# PentaFnord_LedBoard_0_91.net
KiCad netlist of a schematic drawn in EAGLE
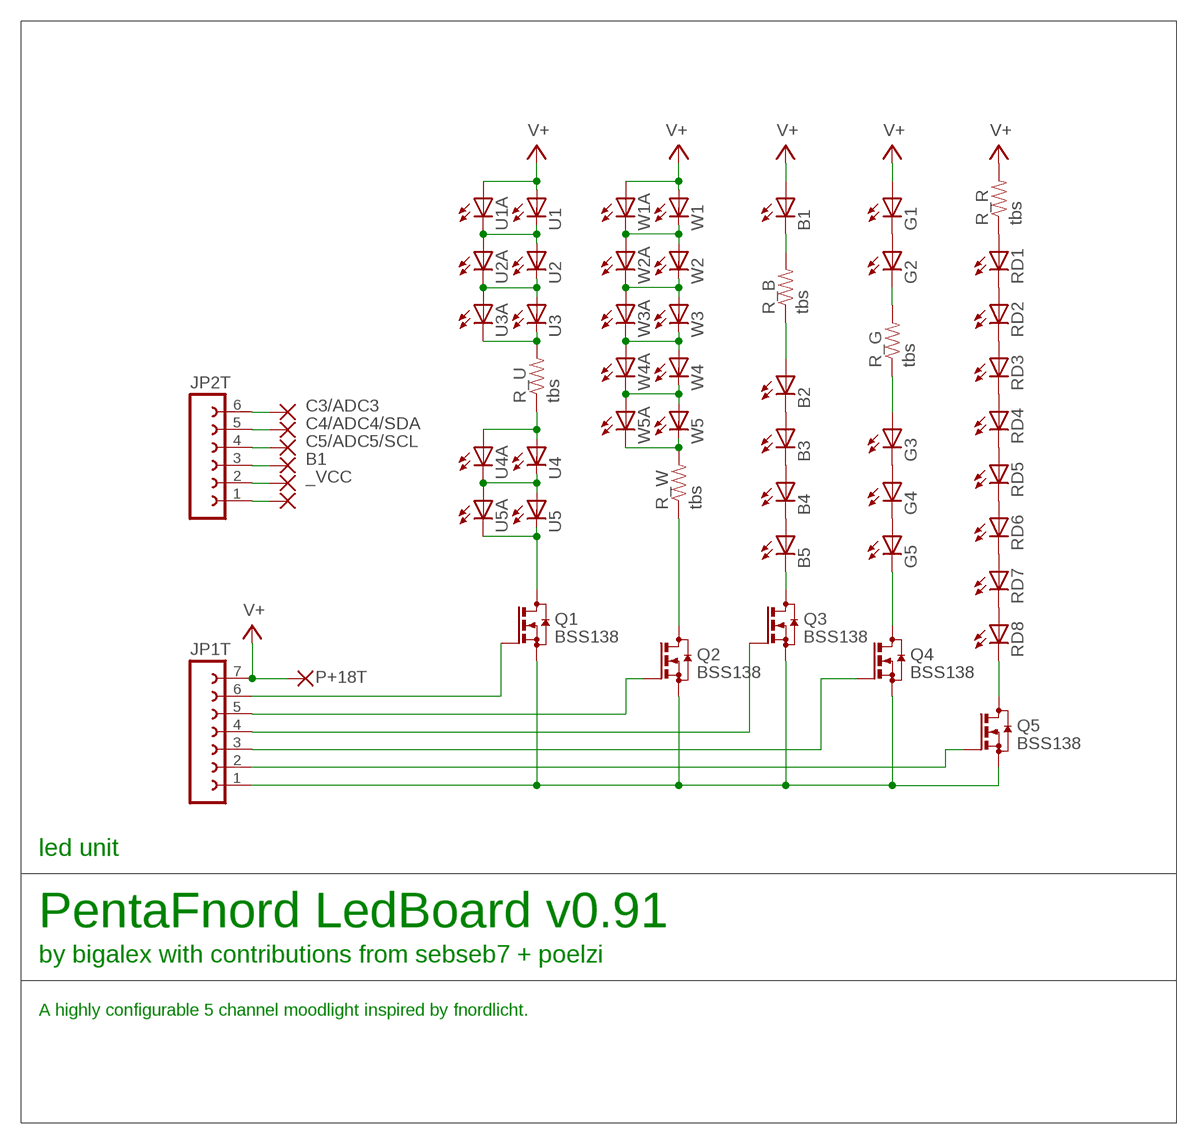
[diagram p0: schematic, sheet 1]

(export (version "E")
  (design (tool "Eeschema 10.0.6"))
  (components
    (comp (ref "B1")
      (value "LED5MM")
      (footprint "eagle-import:LED5MM")
      (libsource (lib "eagle-import") (part "LED5MM"))
    )
    (comp (ref "B2")
      (value "LED5MM")
      (footprint "eagle-import:LED5MM")
      (libsource (lib "eagle-import") (part "LED5MM"))
    )
    (comp (ref "B3")
      (value "LED5MM")
      (footprint "eagle-import:LED5MM")
      (libsource (lib "eagle-import") (part "LED5MM"))
    )
    (comp (ref "B4")
      (value "LED5MM")
      (footprint "eagle-import:LED5MM")
      (libsource (lib "eagle-import") (part "LED5MM"))
    )
    (comp (ref "B5")
      (value "LED5MM")
      (footprint "eagle-import:LED5MM")
      (libsource (lib "eagle-import") (part "LED5MM"))
    )
    (comp (ref "G1")
      (value "LED5MM")
      (footprint "eagle-import:LED5MM")
      (libsource (lib "eagle-import") (part "LED5MM"))
    )
    (comp (ref "G2")
      (value "LED5MM")
      (footprint "eagle-import:LED5MM")
      (libsource (lib "eagle-import") (part "LED5MM"))
    )
    (comp (ref "G3")
      (value "LED5MM")
      (footprint "eagle-import:LED5MM")
      (libsource (lib "eagle-import") (part "LED5MM"))
    )
    (comp (ref "G4")
      (value "LED5MM")
      (footprint "eagle-import:LED5MM")
      (libsource (lib "eagle-import") (part "LED5MM"))
    )
    (comp (ref "G5")
      (value "LED5MM")
      (footprint "eagle-import:LED5MM")
      (libsource (lib "eagle-import") (part "LED5MM"))
    )
    (comp (ref "JP1T")
      (value "FE07-1")
      (footprint "eagle-import:FE07")
      (libsource (lib "eagle-import") (part "FE07-1"))
    )
    (comp (ref "JP2T")
      (value "FE06-1")
      (footprint "eagle-import:FE06")
      (libsource (lib "eagle-import") (part "FE06-1"))
    )
    (comp (ref "P+5T")
      (value "WIREPAD2,54/0,8")
      (footprint "eagle-import:2,54_0,8")
      (libsource (lib "eagle-import") (part "WIREPAD2,54/0,8"))
    )
    (comp (ref "P+18T")
      (value "WIREPAD2,54/0,8")
      (footprint "eagle-import:2,54_0,8")
      (libsource (lib "eagle-import") (part "WIREPAD2,54/0,8"))
    )
    (comp (ref "PB1T")
      (value "WIREPAD2,54/0,8")
      (footprint "eagle-import:2,54_0,8")
      (libsource (lib "eagle-import") (part "WIREPAD2,54/0,8"))
    )
    (comp (ref "PC3T")
      (value "WIREPAD2,54/0,8")
      (footprint "eagle-import:2,54_0,8")
      (libsource (lib "eagle-import") (part "WIREPAD2,54/0,8"))
    )
    (comp (ref "PC4T")
      (value "WIREPAD2,54/0,8")
      (footprint "eagle-import:2,54_0,8")
      (libsource (lib "eagle-import") (part "WIREPAD2,54/0,8"))
    )
    (comp (ref "PC5T")
      (value "WIREPAD2,54/0,8")
      (footprint "eagle-import:2,54_0,8")
      (libsource (lib "eagle-import") (part "WIREPAD2,54/0,8"))
    )
    (comp (ref "PGNDT1")
      (value "WIREPAD2,54/0,8")
      (footprint "eagle-import:2,54_0,8")
      (libsource (lib "eagle-import") (part "WIREPAD2,54/0,8"))
    )
    (comp (ref "Q1")
      (value "BSS138")
      (footprint "eagle-import:SOT23")
      (libsource (lib "eagle-import") (part "BSS123"))
    )
    (comp (ref "Q2")
      (value "BSS138")
      (footprint "eagle-import:SOT23")
      (libsource (lib "eagle-import") (part "BSS123"))
    )
    (comp (ref "Q3")
      (value "BSS138")
      (footprint "eagle-import:SOT23")
      (libsource (lib "eagle-import") (part "BSS123"))
    )
    (comp (ref "Q4")
      (value "BSS138")
      (footprint "eagle-import:SOT23")
      (libsource (lib "eagle-import") (part "BSS123"))
    )
    (comp (ref "Q5")
      (value "BSS138")
      (footprint "eagle-import:SOT23")
      (libsource (lib "eagle-import") (part "BSS123"))
    )
    (comp (ref "RD1")
      (value "LED5MM")
      (footprint "eagle-import:LED5MM")
      (libsource (lib "eagle-import") (part "LED5MM"))
    )
    (comp (ref "RD2")
      (value "LED5MM")
      (footprint "eagle-import:LED5MM")
      (libsource (lib "eagle-import") (part "LED5MM"))
    )
    (comp (ref "RD3")
      (value "LED5MM")
      (footprint "eagle-import:LED5MM")
      (libsource (lib "eagle-import") (part "LED5MM"))
    )
    (comp (ref "RD4")
      (value "LED5MM")
      (footprint "eagle-import:LED5MM")
      (libsource (lib "eagle-import") (part "LED5MM"))
    )
    (comp (ref "RD5")
      (value "LED5MM")
      (footprint "eagle-import:LED5MM")
      (libsource (lib "eagle-import") (part "LED5MM"))
    )
    (comp (ref "RD6")
      (value "LED5MM")
      (footprint "eagle-import:LED5MM")
      (libsource (lib "eagle-import") (part "LED5MM"))
    )
    (comp (ref "RD7")
      (value "LED5MM")
      (footprint "eagle-import:LED5MM")
      (libsource (lib "eagle-import") (part "LED5MM"))
    )
    (comp (ref "RD8")
      (value "LED5MM")
      (footprint "eagle-import:LED5MM")
      (libsource (lib "eagle-import") (part "LED5MM"))
    )
    (comp (ref "R_B")
      (value "tbs")
      (footprint "eagle-import:1206")
      (libsource (lib "eagle-import") (part "RESISTOR1206"))
    )
    (comp (ref "R_G")
      (value "tbs")
      (footprint "eagle-import:1206")
      (libsource (lib "eagle-import") (part "RESISTOR1206"))
    )
    (comp (ref "R_R")
      (value "tbs")
      (footprint "eagle-import:1206")
      (libsource (lib "eagle-import") (part "RESISTOR1206"))
    )
    (comp (ref "R_U")
      (value "tbs")
      (footprint "eagle-import:1206")
      (libsource (lib "eagle-import") (part "RESISTOR1206"))
    )
    (comp (ref "R_W")
      (value "tbs")
      (footprint "eagle-import:1206")
      (libsource (lib "eagle-import") (part "RESISTOR1206"))
    )
    (comp (ref "U1")
      (value "NICHIA_NSSL157T-H3")
      (footprint "eagle-import:PLCC2")
      (libsource (lib "eagle-import") (part "LED_PLCC2"))
    )
    (comp (ref "U1A")
      (value "LED5MM")
      (footprint "eagle-import:LED5MM")
      (libsource (lib "eagle-import") (part "LED5MM"))
    )
    (comp (ref "U2")
      (value "NICHIA_NSSL157T-H3")
      (footprint "eagle-import:PLCC2")
      (libsource (lib "eagle-import") (part "LED_PLCC2"))
    )
    (comp (ref "U2A")
      (value "LED5MM")
      (footprint "eagle-import:LED5MM")
      (libsource (lib "eagle-import") (part "LED5MM"))
    )
    (comp (ref "U3")
      (value "NICHIA_NSSL157T-H3")
      (footprint "eagle-import:PLCC2")
      (libsource (lib "eagle-import") (part "LED_PLCC2"))
    )
    (comp (ref "U3A")
      (value "LED5MM")
      (footprint "eagle-import:LED5MM")
      (libsource (lib "eagle-import") (part "LED5MM"))
    )
    (comp (ref "U4")
      (value "NICHIA_NSSL157T-H3")
      (footprint "eagle-import:PLCC2")
      (libsource (lib "eagle-import") (part "LED_PLCC2"))
    )
    (comp (ref "U4A")
      (value "LED5MM")
      (footprint "eagle-import:LED5MM")
      (libsource (lib "eagle-import") (part "LED5MM"))
    )
    (comp (ref "U5")
      (value "NICHIA_NSSL157T-H3")
      (footprint "eagle-import:PLCC2")
      (libsource (lib "eagle-import") (part "LED_PLCC2"))
    )
    (comp (ref "U5A")
      (value "LED5MM")
      (footprint "eagle-import:LED5MM")
      (libsource (lib "eagle-import") (part "LED5MM"))
    )
    (comp (ref "W1")
      (value "NICHIA_NSSL157T-H3")
      (footprint "eagle-import:NICHIA_NSSL157T-H3")
      (libsource (lib "eagle-import") (part "NICHIA_NSSL157T-H3"))
    )
    (comp (ref "W1A")
      (value "LED5MM")
      (footprint "eagle-import:LED5MM")
      (libsource (lib "eagle-import") (part "LED5MM"))
    )
    (comp (ref "W2")
      (value "NICHIA_NSSL157T-H3")
      (footprint "eagle-import:NICHIA_NSSL157T-H3")
      (libsource (lib "eagle-import") (part "NICHIA_NSSL157T-H3"))
    )
    (comp (ref "W2A")
      (value "LED5MM")
      (footprint "eagle-import:LED5MM")
      (libsource (lib "eagle-import") (part "LED5MM"))
    )
    (comp (ref "W3")
      (value "NICHIA_NSSL157T-H3")
      (footprint "eagle-import:NICHIA_NSSL157T-H3")
      (libsource (lib "eagle-import") (part "NICHIA_NSSL157T-H3"))
    )
    (comp (ref "W3A")
      (value "LED5MM")
      (footprint "eagle-import:LED5MM")
      (libsource (lib "eagle-import") (part "LED5MM"))
    )
    (comp (ref "W4")
      (value "NICHIA_NSSL157T-H3")
      (footprint "eagle-import:NICHIA_NSSL157T-H3")
      (libsource (lib "eagle-import") (part "NICHIA_NSSL157T-H3"))
    )
    (comp (ref "W4A")
      (value "LED5MM")
      (footprint "eagle-import:LED5MM")
      (libsource (lib "eagle-import") (part "LED5MM"))
    )
    (comp (ref "W5")
      (value "NICHIA_NSSL157T-H3")
      (footprint "eagle-import:NICHIA_NSSL157T-H3")
      (libsource (lib "eagle-import") (part "NICHIA_NSSL157T-H3"))
    )
    (comp (ref "W5A")
      (value "LED5MM")
      (footprint "eagle-import:LED5MM")
      (libsource (lib "eagle-import") (part "LED5MM"))
    )
  )
  (nets
    (net (code "1") (name "/B1") (class "Default")
      (node (ref "JP2T") (pin "3") (pinfunction "3_3") (pintype "passive"))
      (node (ref "PB1T") (pin "1") (pinfunction "P_1") (pintype "passive"))
    )
    (net (code "2") (name "/C3{slash}ADC3") (class "Default")
      (node (ref "JP2T") (pin "6") (pinfunction "6_6") (pintype "passive"))
      (node (ref "PC3T") (pin "1") (pinfunction "P_1") (pintype "passive"))
    )
    (net (code "3") (name "/C4{slash}ADC4{slash}SDA") (class "Default")
      (node (ref "JP2T") (pin "5") (pinfunction "5_5") (pintype "passive"))
      (node (ref "PC4T") (pin "1") (pinfunction "P_1") (pintype "passive"))
    )
    (net (code "4") (name "/C5{slash}ADC5{slash}SCL") (class "Default")
      (node (ref "JP2T") (pin "4") (pinfunction "4_4") (pintype "passive"))
      (node (ref "PC5T") (pin "1") (pinfunction "P_1") (pintype "passive"))
    )
    (net (code "5") (name "/GND_T") (class "Default")
      (node (ref "JP1T") (pin "1") (pinfunction "1_1") (pintype "passive"))
      (node (ref "JP2T") (pin "1") (pinfunction "1_1") (pintype "passive"))
      (node (ref "PGNDT1") (pin "1") (pinfunction "P_1") (pintype "passive"))
      (node (ref "Q1") (pin "2") (pinfunction "S_2") (pintype "passive"))
      (node (ref "Q2") (pin "2") (pinfunction "S_2") (pintype "passive"))
      (node (ref "Q3") (pin "2") (pinfunction "S_2") (pintype "passive"))
      (node (ref "Q4") (pin "2") (pinfunction "S_2") (pintype "passive"))
      (node (ref "Q5") (pin "2") (pinfunction "S_2") (pintype "passive"))
    )
    (net (code "6") (name "/_VCC") (class "Default")
      (node (ref "JP2T") (pin "2") (pinfunction "2_2") (pintype "passive"))
      (node (ref "P+5T") (pin "1") (pinfunction "P_1") (pintype "passive"))
    )
    (net (code "7") (name "Net-(B1-C)") (class "Default")
      (node (ref "B1") (pin "K") (pinfunction "C_K") (pintype "passive"))
      (node (ref "R_B") (pin "2") (pinfunction "2_2") (pintype "passive"))
    )
    (net (code "8") (name "Net-(B2-C)") (class "Default")
      (node (ref "B2") (pin "K") (pinfunction "C_K") (pintype "passive"))
      (node (ref "B3") (pin "A") (pinfunction "A_A") (pintype "passive"))
    )
    (net (code "9") (name "Net-(B2-PadA)") (class "Default")
      (node (ref "B2") (pin "A") (pinfunction "A_A") (pintype "passive"))
      (node (ref "R_B") (pin "1") (pinfunction "1_1") (pintype "passive"))
    )
    (net (code "10") (name "Net-(B3-C)") (class "Default")
      (node (ref "B3") (pin "K") (pinfunction "C_K") (pintype "passive"))
      (node (ref "B4") (pin "A") (pinfunction "A_A") (pintype "passive"))
    )
    (net (code "11") (name "Net-(B4-C)") (class "Default")
      (node (ref "B4") (pin "K") (pinfunction "C_K") (pintype "passive"))
      (node (ref "B5") (pin "A") (pinfunction "A_A") (pintype "passive"))
    )
    (net (code "12") (name "Net-(B5-C)") (class "Default")
      (node (ref "B5") (pin "K") (pinfunction "C_K") (pintype "passive"))
      (node (ref "Q3") (pin "3") (pinfunction "D_3") (pintype "passive"))
    )
    (net (code "13") (name "Net-(G1-C)") (class "Default")
      (node (ref "G1") (pin "K") (pinfunction "C_K") (pintype "passive"))
      (node (ref "G2") (pin "A") (pinfunction "A_A") (pintype "passive"))
    )
    (net (code "14") (name "Net-(G2-C)") (class "Default")
      (node (ref "G2") (pin "K") (pinfunction "C_K") (pintype "passive"))
      (node (ref "R_G") (pin "2") (pinfunction "2_2") (pintype "passive"))
    )
    (net (code "15") (name "Net-(G3-C)") (class "Default")
      (node (ref "G3") (pin "K") (pinfunction "C_K") (pintype "passive"))
      (node (ref "G4") (pin "A") (pinfunction "A_A") (pintype "passive"))
    )
    (net (code "16") (name "Net-(G3-PadA)") (class "Default")
      (node (ref "G3") (pin "A") (pinfunction "A_A") (pintype "passive"))
      (node (ref "R_G") (pin "1") (pinfunction "1_1") (pintype "passive"))
    )
    (net (code "17") (name "Net-(G4-C)") (class "Default")
      (node (ref "G4") (pin "K") (pinfunction "C_K") (pintype "passive"))
      (node (ref "G5") (pin "A") (pinfunction "A_A") (pintype "passive"))
    )
    (net (code "18") (name "Net-(G5-C)") (class "Default")
      (node (ref "G5") (pin "K") (pinfunction "C_K") (pintype "passive"))
      (node (ref "Q4") (pin "3") (pinfunction "D_3") (pintype "passive"))
    )
    (net (code "19") (name "Net-(Q1-D)") (class "Default")
      (node (ref "Q1") (pin "3") (pinfunction "D_3") (pintype "passive"))
      (node (ref "U5") (pin "P$1") (pinfunction "C_P$1") (pintype "passive"))
      (node (ref "U5A") (pin "K") (pinfunction "C_K") (pintype "passive"))
    )
    (net (code "20") (name "Net-(Q1-G)") (class "Default")
      (node (ref "JP1T") (pin "6") (pinfunction "6_6") (pintype "passive"))
      (node (ref "Q1") (pin "1") (pinfunction "G_1") (pintype "passive"))
    )
    (net (code "21") (name "Net-(Q2-D)") (class "Default")
      (node (ref "Q2") (pin "3") (pinfunction "D_3") (pintype "passive"))
      (node (ref "R_W") (pin "1") (pinfunction "1_1") (pintype "passive"))
    )
    (net (code "22") (name "Net-(Q2-G)") (class "Default")
      (node (ref "JP1T") (pin "5") (pinfunction "5_5") (pintype "passive"))
      (node (ref "Q2") (pin "1") (pinfunction "G_1") (pintype "passive"))
    )
    (net (code "23") (name "Net-(Q3-G)") (class "Default")
      (node (ref "JP1T") (pin "4") (pinfunction "4_4") (pintype "passive"))
      (node (ref "Q3") (pin "1") (pinfunction "G_1") (pintype "passive"))
    )
    (net (code "24") (name "Net-(Q4-G)") (class "Default")
      (node (ref "JP1T") (pin "3") (pinfunction "3_3") (pintype "passive"))
      (node (ref "Q4") (pin "1") (pinfunction "G_1") (pintype "passive"))
    )
    (net (code "25") (name "Net-(Q5-D)") (class "Default")
      (node (ref "Q5") (pin "3") (pinfunction "D_3") (pintype "passive"))
      (node (ref "RD8") (pin "K") (pinfunction "C_K") (pintype "passive"))
    )
    (net (code "26") (name "Net-(Q5-G)") (class "Default")
      (node (ref "JP1T") (pin "2") (pinfunction "2_2") (pintype "passive"))
      (node (ref "Q5") (pin "1") (pinfunction "G_1") (pintype "passive"))
    )
    (net (code "27") (name "Net-(RD1-C)") (class "Default")
      (node (ref "RD1") (pin "K") (pinfunction "C_K") (pintype "passive"))
      (node (ref "RD2") (pin "A") (pinfunction "A_A") (pintype "passive"))
    )
    (net (code "28") (name "Net-(RD1-PadA)") (class "Default")
      (node (ref "RD1") (pin "A") (pinfunction "A_A") (pintype "passive"))
      (node (ref "R_R") (pin "1") (pinfunction "1_1") (pintype "passive"))
    )
    (net (code "29") (name "Net-(RD2-C)") (class "Default")
      (node (ref "RD2") (pin "K") (pinfunction "C_K") (pintype "passive"))
      (node (ref "RD3") (pin "A") (pinfunction "A_A") (pintype "passive"))
    )
    (net (code "30") (name "Net-(RD3-C)") (class "Default")
      (node (ref "RD3") (pin "K") (pinfunction "C_K") (pintype "passive"))
      (node (ref "RD4") (pin "A") (pinfunction "A_A") (pintype "passive"))
    )
    (net (code "31") (name "Net-(RD4-C)") (class "Default")
      (node (ref "RD4") (pin "K") (pinfunction "C_K") (pintype "passive"))
      (node (ref "RD5") (pin "A") (pinfunction "A_A") (pintype "passive"))
    )
    (net (code "32") (name "Net-(RD5-C)") (class "Default")
      (node (ref "RD5") (pin "K") (pinfunction "C_K") (pintype "passive"))
      (node (ref "RD6") (pin "A") (pinfunction "A_A") (pintype "passive"))
    )
    (net (code "33") (name "Net-(RD6-C)") (class "Default")
      (node (ref "RD6") (pin "K") (pinfunction "C_K") (pintype "passive"))
      (node (ref "RD7") (pin "A") (pinfunction "A_A") (pintype "passive"))
    )
    (net (code "34") (name "Net-(RD7-C)") (class "Default")
      (node (ref "RD7") (pin "K") (pinfunction "C_K") (pintype "passive"))
      (node (ref "RD8") (pin "A") (pinfunction "A_A") (pintype "passive"))
    )
    (net (code "35") (name "Net-(U1-C)") (class "Default")
      (node (ref "U1") (pin "P$1") (pinfunction "C_P$1") (pintype "passive"))
      (node (ref "U1A") (pin "K") (pinfunction "C_K") (pintype "passive"))
      (node (ref "U2") (pin "P$2") (pinfunction "A_P$2") (pintype "passive"))
      (node (ref "U2A") (pin "A") (pinfunction "A_A") (pintype "passive"))
    )
    (net (code "36") (name "Net-(U2-C)") (class "Default")
      (node (ref "U2") (pin "P$1") (pinfunction "C_P$1") (pintype "passive"))
      (node (ref "U2A") (pin "K") (pinfunction "C_K") (pintype "passive"))
      (node (ref "U3") (pin "P$2") (pinfunction "A_P$2") (pintype "passive"))
      (node (ref "U3A") (pin "A") (pinfunction "A_A") (pintype "passive"))
    )
    (net (code "37") (name "Net-(U3-C)") (class "Default")
      (node (ref "R_U") (pin "2") (pinfunction "2_2") (pintype "passive"))
      (node (ref "U3") (pin "P$1") (pinfunction "C_P$1") (pintype "passive"))
      (node (ref "U3A") (pin "K") (pinfunction "C_K") (pintype "passive"))
    )
    (net (code "38") (name "Net-(U4-A)") (class "Default")
      (node (ref "R_U") (pin "1") (pinfunction "1_1") (pintype "passive"))
      (node (ref "U4") (pin "P$2") (pinfunction "A_P$2") (pintype "passive"))
      (node (ref "U4A") (pin "A") (pinfunction "A_A") (pintype "passive"))
    )
    (net (code "39") (name "Net-(U4-C)") (class "Default")
      (node (ref "U4") (pin "P$1") (pinfunction "C_P$1") (pintype "passive"))
      (node (ref "U4A") (pin "K") (pinfunction "C_K") (pintype "passive"))
      (node (ref "U5") (pin "P$2") (pinfunction "A_P$2") (pintype "passive"))
      (node (ref "U5A") (pin "A") (pinfunction "A_A") (pintype "passive"))
    )
    (net (code "40") (name "Net-(W1-C)") (class "Default")
      (node (ref "W1") (pin "K@1") (pinfunction "C_K@1") (pintype "passive"))
      (node (ref "W1A") (pin "K") (pinfunction "C_K") (pintype "passive"))
      (node (ref "W2") (pin "A@2") (pinfunction "A_A@2") (pintype "passive"))
      (node (ref "W2A") (pin "A") (pinfunction "A_A") (pintype "passive"))
    )
    (net (code "41") (name "Net-(W2-C)") (class "Default")
      (node (ref "W2") (pin "K@1") (pinfunction "C_K@1") (pintype "passive"))
      (node (ref "W2A") (pin "K") (pinfunction "C_K") (pintype "passive"))
      (node (ref "W3") (pin "A@2") (pinfunction "A_A@2") (pintype "passive"))
      (node (ref "W3A") (pin "A") (pinfunction "A_A") (pintype "passive"))
    )
    (net (code "42") (name "Net-(W3-C)") (class "Default")
      (node (ref "W3") (pin "K@1") (pinfunction "C_K@1") (pintype "passive"))
      (node (ref "W3A") (pin "K") (pinfunction "C_K") (pintype "passive"))
      (node (ref "W4") (pin "A@2") (pinfunction "A_A@2") (pintype "passive"))
      (node (ref "W4A") (pin "A") (pinfunction "A_A") (pintype "passive"))
    )
    (net (code "43") (name "Net-(W4-C)") (class "Default")
      (node (ref "W4") (pin "K@1") (pinfunction "C_K@1") (pintype "passive"))
      (node (ref "W4A") (pin "K") (pinfunction "C_K") (pintype "passive"))
      (node (ref "W5") (pin "A@2") (pinfunction "A_A@2") (pintype "passive"))
      (node (ref "W5A") (pin "A") (pinfunction "A_A") (pintype "passive"))
    )
    (net (code "44") (name "Net-(W5-C)") (class "Default")
      (node (ref "R_W") (pin "2") (pinfunction "2_2") (pintype "passive"))
      (node (ref "W5") (pin "K@1") (pinfunction "C_K@1") (pintype "passive"))
      (node (ref "W5A") (pin "K") (pinfunction "C_K") (pintype "passive"))
    )
    (net (code "45") (name "V+") (class "Default")
      (node (ref "B1") (pin "A") (pinfunction "A_A") (pintype "passive"))
      (node (ref "G1") (pin "A") (pinfunction "A_A") (pintype "passive"))
      (node (ref "JP1T") (pin "7") (pinfunction "7_7") (pintype "passive"))
      (node (ref "P+18T") (pin "1") (pinfunction "P_1") (pintype "passive"))
      (node (ref "R_R") (pin "2") (pinfunction "2_2") (pintype "passive"))
      (node (ref "U1") (pin "P$2") (pinfunction "A_P$2") (pintype "passive"))
      (node (ref "U1A") (pin "A") (pinfunction "A_A") (pintype "passive"))
      (node (ref "W1") (pin "A@2") (pinfunction "A_A@2") (pintype "passive"))
      (node (ref "W1A") (pin "A") (pinfunction "A_A") (pintype "passive"))
    )
  )
)
